# fishnet-0_5.net
KiCad netlist of a schematic drawn in EAGLE
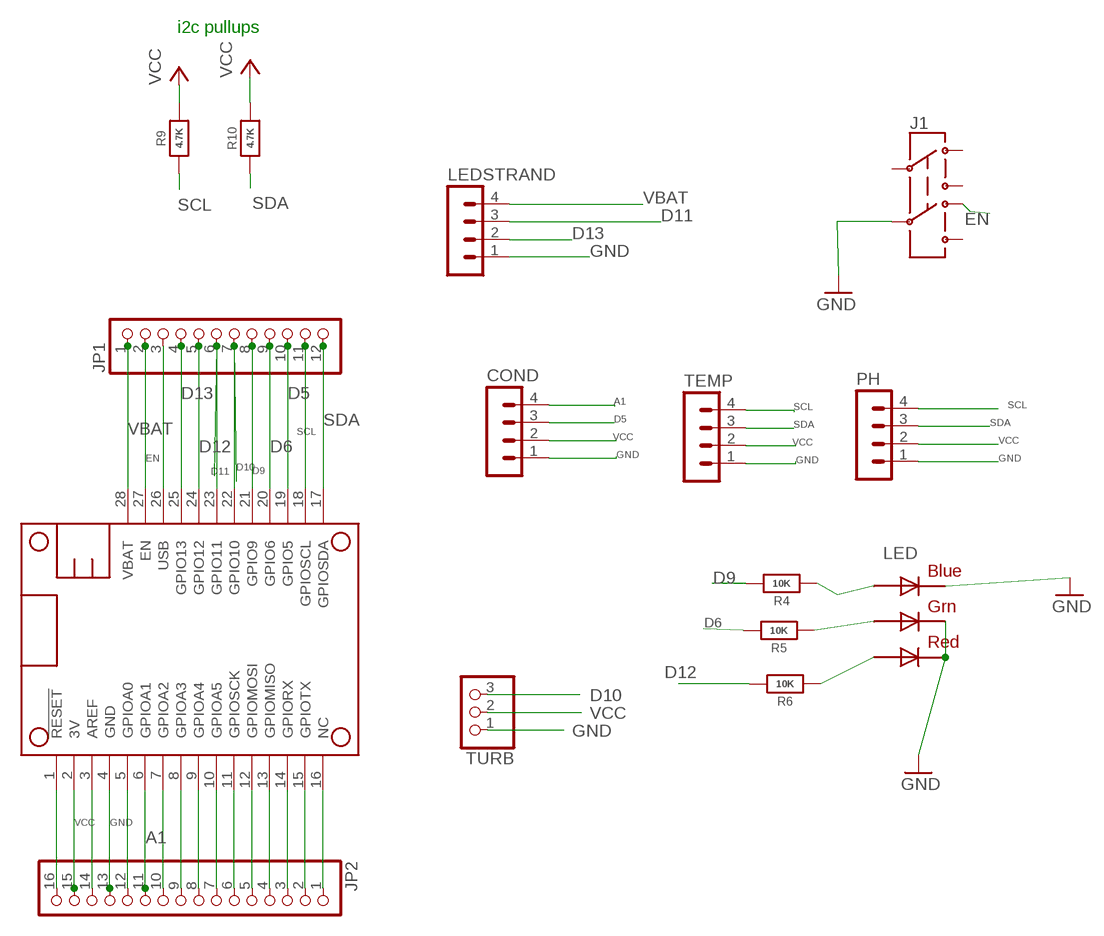
[diagram p0: schematic, sheet 1]

(export (version "E")
  (design (tool "Eeschema 10.0.6"))
  (components
    (comp (ref "COND")
      (value "MA04-1")
      (footprint "eagle-import:MA04-1")
      (libsource (lib "eagle-import") (part "MA04-1"))
    )
    (comp (ref "J1")
      (value "AYZ0202")
      (footprint "eagle-import:AYZ0202")
      (libsource (lib "eagle-import") (part "AYZ0202"))
    )
    (comp (ref "JP1")
      (value "PINHD-1X12")
      (footprint "eagle-import:1X12")
      (libsource (lib "eagle-import") (part "PINHD-1X12"))
    )
    (comp (ref "JP2")
      (value "PINHD-1X16")
      (footprint "eagle-import:1X16")
      (libsource (lib "eagle-import") (part "PINHD-1X16"))
    )
    (comp (ref "LED")
      (value "RGBLED5050")
      (footprint "eagle-import:RGBLED5050")
      (libsource (lib "eagle-import") (part "RGBLED5050"))
    )
    (comp (ref "LEDSTRAND")
      (value "MA04-1")
      (footprint "eagle-import:MA04-1")
      (libsource (lib "eagle-import") (part "MA04-1"))
    )
    (comp (ref "MS1")
      (value "FEATHERWING")
      (footprint "eagle-import:FEATHERWING")
      (libsource (lib "eagle-import") (part "FEATHERWING"))
    )
    (comp (ref "PH")
      (value "MA04-1")
      (footprint "eagle-import:MA04-1")
      (fields (field (name "OC_FARNELL") "unknown") (field (name "OC_NEWARK") "unknown"))
      (libsource (lib "eagle-import") (part "MA04-1"))
    )
    (comp (ref "R4")
      (value "10K")
      (footprint "eagle-import:0603-NO")
      (libsource (lib "eagle-import") (part "RESISTOR_0603_NOOUT"))
    )
    (comp (ref "R5")
      (value "10K")
      (footprint "eagle-import:0603-NO")
      (libsource (lib "eagle-import") (part "RESISTOR_0603_NOOUT"))
    )
    (comp (ref "R6")
      (value "10K")
      (footprint "eagle-import:0603-NO")
      (libsource (lib "eagle-import") (part "RESISTOR_0603_NOOUT"))
    )
    (comp (ref "R9")
      (value "4.7K")
      (footprint "eagle-import:0603-NO")
      (libsource (lib "eagle-import") (part "RESISTOR_0603_NOOUT"))
    )
    (comp (ref "R10")
      (value "4.7K")
      (footprint "eagle-import:0603-NO")
      (libsource (lib "eagle-import") (part "RESISTOR_0603_NOOUT"))
    )
    (comp (ref "TEMP")
      (value "MA04-1")
      (footprint "eagle-import:MA04-1")
      (libsource (lib "eagle-import") (part "MA04-1"))
    )
    (comp (ref "TURB")
      (value "PINHD-1X3")
      (footprint "eagle-import:1X03")
      (libsource (lib "eagle-import") (part "PINHD-1X3"))
    )
  )
  (nets
    (net (code "1") (name "/A1") (class "Default")
      (node (ref "COND") (pin "4") (pinfunction "4_4") (pintype "passive"))
      (node (ref "JP2") (pin "11") (pinfunction "11_11") (pintype "passive"))
      (node (ref "MS1") (pin "6") (pinfunction "GPIOA1_6") (pintype "bidirectional"))
    )
    (net (code "2") (name "/D5") (class "Default")
      (node (ref "COND") (pin "3") (pinfunction "3_3") (pintype "passive"))
      (node (ref "JP1") (pin "10") (pinfunction "10_10") (pintype "passive"))
      (node (ref "MS1") (pin "19") (pinfunction "GPIO5_19") (pintype "bidirectional"))
    )
    (net (code "3") (name "/D6") (class "Default")
      (node (ref "JP1") (pin "9") (pinfunction "9_9") (pintype "passive"))
      (node (ref "MS1") (pin "20") (pinfunction "GPIO6_20") (pintype "bidirectional"))
      (node (ref "R5") (pin "2") (pinfunction "2_2") (pintype "passive"))
    )
    (net (code "4") (name "/D9") (class "Default")
      (node (ref "JP1") (pin "8") (pinfunction "8_8") (pintype "passive"))
      (node (ref "MS1") (pin "21") (pinfunction "GPIO9_21") (pintype "bidirectional"))
      (node (ref "R4") (pin "2") (pinfunction "2_2") (pintype "passive"))
    )
    (net (code "5") (name "/D10") (class "Default")
      (node (ref "JP1") (pin "7") (pinfunction "7_7") (pintype "passive"))
      (node (ref "MS1") (pin "22") (pinfunction "GPIO10_22") (pintype "bidirectional"))
      (node (ref "TURB") (pin "3") (pinfunction "3_3") (pintype "passive"))
    )
    (net (code "6") (name "/D11") (class "Default")
      (node (ref "JP1") (pin "6") (pinfunction "6_6") (pintype "passive"))
      (node (ref "LEDSTRAND") (pin "3") (pinfunction "3_3") (pintype "passive"))
      (node (ref "MS1") (pin "23") (pinfunction "GPIO11_23") (pintype "bidirectional"))
    )
    (net (code "7") (name "/D12") (class "Default")
      (node (ref "JP1") (pin "5") (pinfunction "5_5") (pintype "passive"))
      (node (ref "MS1") (pin "24") (pinfunction "GPIO12_24") (pintype "bidirectional"))
      (node (ref "R6") (pin "2") (pinfunction "2_2") (pintype "passive"))
    )
    (net (code "8") (name "/D13") (class "Default")
      (node (ref "JP1") (pin "4") (pinfunction "4_4") (pintype "passive"))
      (node (ref "LEDSTRAND") (pin "2") (pinfunction "2_2") (pintype "passive"))
      (node (ref "MS1") (pin "25") (pinfunction "GPIO13_25") (pintype "bidirectional"))
    )
    (net (code "9") (name "/EN") (class "Default")
      (node (ref "J1") (pin "6") (pinfunction "4_6") (pintype "bidirectional"))
      (node (ref "JP1") (pin "2") (pinfunction "2_2") (pintype "passive"))
      (node (ref "MS1") (pin "27") (pinfunction "EN_27") (pintype "passive"))
    )
    (net (code "10") (name "/SCL") (class "Default")
      (node (ref "JP1") (pin "11") (pinfunction "11_11") (pintype "passive"))
      (node (ref "MS1") (pin "18") (pinfunction "GPIOSCL_18") (pintype "bidirectional"))
      (node (ref "PH") (pin "4") (pinfunction "4_4") (pintype "passive"))
      (node (ref "R9") (pin "1") (pinfunction "1_1") (pintype "passive"))
      (node (ref "TEMP") (pin "4") (pinfunction "4_4") (pintype "passive"))
    )
    (net (code "11") (name "/SDA") (class "Default")
      (node (ref "JP1") (pin "12") (pinfunction "12_12") (pintype "passive"))
      (node (ref "MS1") (pin "17") (pinfunction "GPIOSDA_17") (pintype "bidirectional"))
      (node (ref "PH") (pin "3") (pinfunction "3_3") (pintype "passive"))
      (node (ref "R10") (pin "1") (pinfunction "1_1") (pintype "passive"))
      (node (ref "TEMP") (pin "3") (pinfunction "3_3") (pintype "passive"))
    )
    (net (code "12") (name "/VBAT") (class "Default")
      (node (ref "JP1") (pin "1") (pinfunction "1_1") (pintype "passive"))
      (node (ref "LEDSTRAND") (pin "4") (pinfunction "4_4") (pintype "passive"))
      (node (ref "MS1") (pin "28") (pinfunction "VBAT_28") (pintype "power_in"))
    )
    (net (code "13") (name "GND") (class "Default")
      (node (ref "COND") (pin "1") (pinfunction "1_1") (pintype "passive"))
      (node (ref "J1") (pin "5") (pinfunction "5_5") (pintype "bidirectional"))
      (node (ref "JP2") (pin "13") (pinfunction "13_13") (pintype "passive"))
      (node (ref "LED") (pin "4") (pinfunction "BLUE_C_4") (pintype "bidirectional"))
      (node (ref "LED") (pin "5") (pinfunction "RED_C_5") (pintype "bidirectional"))
      (node (ref "LED") (pin "6") (pinfunction "GREEN_C_6") (pintype "bidirectional"))
      (node (ref "LEDSTRAND") (pin "1") (pinfunction "1_1") (pintype "passive"))
      (node (ref "MS1") (pin "4") (pinfunction "GND_4") (pintype "power_in"))
      (node (ref "PH") (pin "1") (pinfunction "1_1") (pintype "passive"))
      (node (ref "TEMP") (pin "1") (pinfunction "1_1") (pintype "passive"))
      (node (ref "TURB") (pin "1") (pinfunction "1_1") (pintype "passive"))
    )
    (net (code "14") (name "Net-(LED-BLUE_A)") (class "Default")
      (node (ref "LED") (pin "3") (pinfunction "BLUE_A_3") (pintype "bidirectional"))
      (node (ref "R4") (pin "1") (pinfunction "1_1") (pintype "passive"))
    )
    (net (code "15") (name "Net-(LED-GREEN_A)") (class "Default")
      (node (ref "LED") (pin "1") (pinfunction "GREEN_A_1") (pintype "bidirectional"))
      (node (ref "R5") (pin "1") (pinfunction "1_1") (pintype "passive"))
    )
    (net (code "16") (name "Net-(LED-RED_A)") (class "Default")
      (node (ref "LED") (pin "2") (pinfunction "RED_A_2") (pintype "bidirectional"))
      (node (ref "R6") (pin "1") (pinfunction "1_1") (pintype "passive"))
    )
    (net (code "17") (name "Net-(MS1-AREF)") (class "Default")
      (node (ref "JP2") (pin "14") (pinfunction "14_14") (pintype "passive"))
      (node (ref "MS1") (pin "3") (pinfunction "AREF_3") (pintype "passive"))
    )
    (net (code "18") (name "Net-(MS1-GPIOA0)") (class "Default")
      (node (ref "JP2") (pin "12") (pinfunction "12_12") (pintype "passive"))
      (node (ref "MS1") (pin "5") (pinfunction "GPIOA0_5") (pintype "bidirectional"))
    )
    (net (code "19") (name "Net-(MS1-GPIOA2)") (class "Default")
      (node (ref "JP2") (pin "10") (pinfunction "10_10") (pintype "passive"))
      (node (ref "MS1") (pin "7") (pinfunction "GPIOA2_7") (pintype "bidirectional"))
    )
    (net (code "20") (name "Net-(MS1-GPIOA3)") (class "Default")
      (node (ref "JP2") (pin "9") (pinfunction "9_9") (pintype "passive"))
      (node (ref "MS1") (pin "8") (pinfunction "GPIOA3_8") (pintype "bidirectional"))
    )
    (net (code "21") (name "Net-(MS1-GPIOA4)") (class "Default")
      (node (ref "JP2") (pin "8") (pinfunction "8_8") (pintype "passive"))
      (node (ref "MS1") (pin "9") (pinfunction "GPIOA4_9") (pintype "bidirectional"))
    )
    (net (code "22") (name "Net-(MS1-GPIOA5)") (class "Default")
      (node (ref "JP2") (pin "7") (pinfunction "7_7") (pintype "passive"))
      (node (ref "MS1") (pin "10") (pinfunction "GPIOA5_10") (pintype "bidirectional"))
    )
    (net (code "23") (name "Net-(MS1-GPIOMISO)") (class "Default")
      (node (ref "JP2") (pin "4") (pinfunction "4_4") (pintype "passive"))
      (node (ref "MS1") (pin "13") (pinfunction "GPIOMISO_13") (pintype "bidirectional"))
    )
    (net (code "24") (name "Net-(MS1-GPIOMOSI)") (class "Default")
      (node (ref "JP2") (pin "5") (pinfunction "5_5") (pintype "passive"))
      (node (ref "MS1") (pin "12") (pinfunction "GPIOMOSI_12") (pintype "bidirectional"))
    )
    (net (code "25") (name "Net-(MS1-GPIORX)") (class "Default")
      (node (ref "JP2") (pin "3") (pinfunction "3_3") (pintype "passive"))
      (node (ref "MS1") (pin "14") (pinfunction "GPIORX_14") (pintype "bidirectional"))
    )
    (net (code "26") (name "Net-(MS1-GPIOSCK)") (class "Default")
      (node (ref "JP2") (pin "6") (pinfunction "6_6") (pintype "passive"))
      (node (ref "MS1") (pin "11") (pinfunction "GPIOSCK_11") (pintype "bidirectional"))
    )
    (net (code "27") (name "Net-(MS1-GPIOTX)") (class "Default")
      (node (ref "JP2") (pin "2") (pinfunction "2_2") (pintype "passive"))
      (node (ref "MS1") (pin "15") (pinfunction "GPIOTX_15") (pintype "bidirectional"))
    )
    (net (code "28") (name "Net-(MS1-NC)") (class "Default")
      (node (ref "JP2") (pin "1") (pinfunction "1_1") (pintype "passive"))
      (node (ref "MS1") (pin "16") (pinfunction "NC_16") (pintype "passive"))
    )
    (net (code "29") (name "Net-(MS1-USB)") (class "Default")
      (node (ref "JP1") (pin "3") (pinfunction "3_3") (pintype "passive"))
      (node (ref "MS1") (pin "26") (pinfunction "USB_26") (pintype "power_in"))
    )
    (net (code "30") (name "Net-(MS1-~{RESET})") (class "Default")
      (node (ref "JP2") (pin "16") (pinfunction "16_16") (pintype "passive"))
      (node (ref "MS1") (pin "1") (pinfunction "~{RESET}_1") (pintype "input"))
    )
    (net (code "31") (name "VCC") (class "Default")
      (node (ref "COND") (pin "2") (pinfunction "2_2") (pintype "passive"))
      (node (ref "JP2") (pin "15") (pinfunction "15_15") (pintype "passive"))
      (node (ref "MS1") (pin "2") (pinfunction "3V_2") (pintype "power_in"))
      (node (ref "PH") (pin "2") (pinfunction "2_2") (pintype "passive"))
      (node (ref "R10") (pin "2") (pinfunction "2_2") (pintype "passive"))
      (node (ref "R9") (pin "2") (pinfunction "2_2") (pintype "passive"))
      (node (ref "TEMP") (pin "2") (pinfunction "2_2") (pintype "passive"))
      (node (ref "TURB") (pin "2") (pinfunction "2_2") (pintype "passive"))
    )
    (net (code "32") (name "unconnected-(J1-1-Pad3)") (class "Default")
      (node (ref "J1") (pin "3") (pinfunction "1_3") (pintype "bidirectional"))
    )
    (net (code "33") (name "unconnected-(J1-3-Pad1)") (class "Default")
      (node (ref "J1") (pin "1") (pinfunction "3_1") (pintype "bidirectional"))
    )
    (net (code "34") (name "unconnected-(J1-6-Pad4)") (class "Default")
      (node (ref "J1") (pin "4") (pinfunction "6_4") (pintype "bidirectional"))
    )
    (net (code "35") (name "unconnected-(J1-Pad2)") (class "Default")
      (node (ref "J1") (pin "2") (pinfunction "2_2") (pintype "bidirectional"))
    )
  )
)
